# paris_relay_rev_C.net
KiCad netlist of a schematic drawn in EAGLE
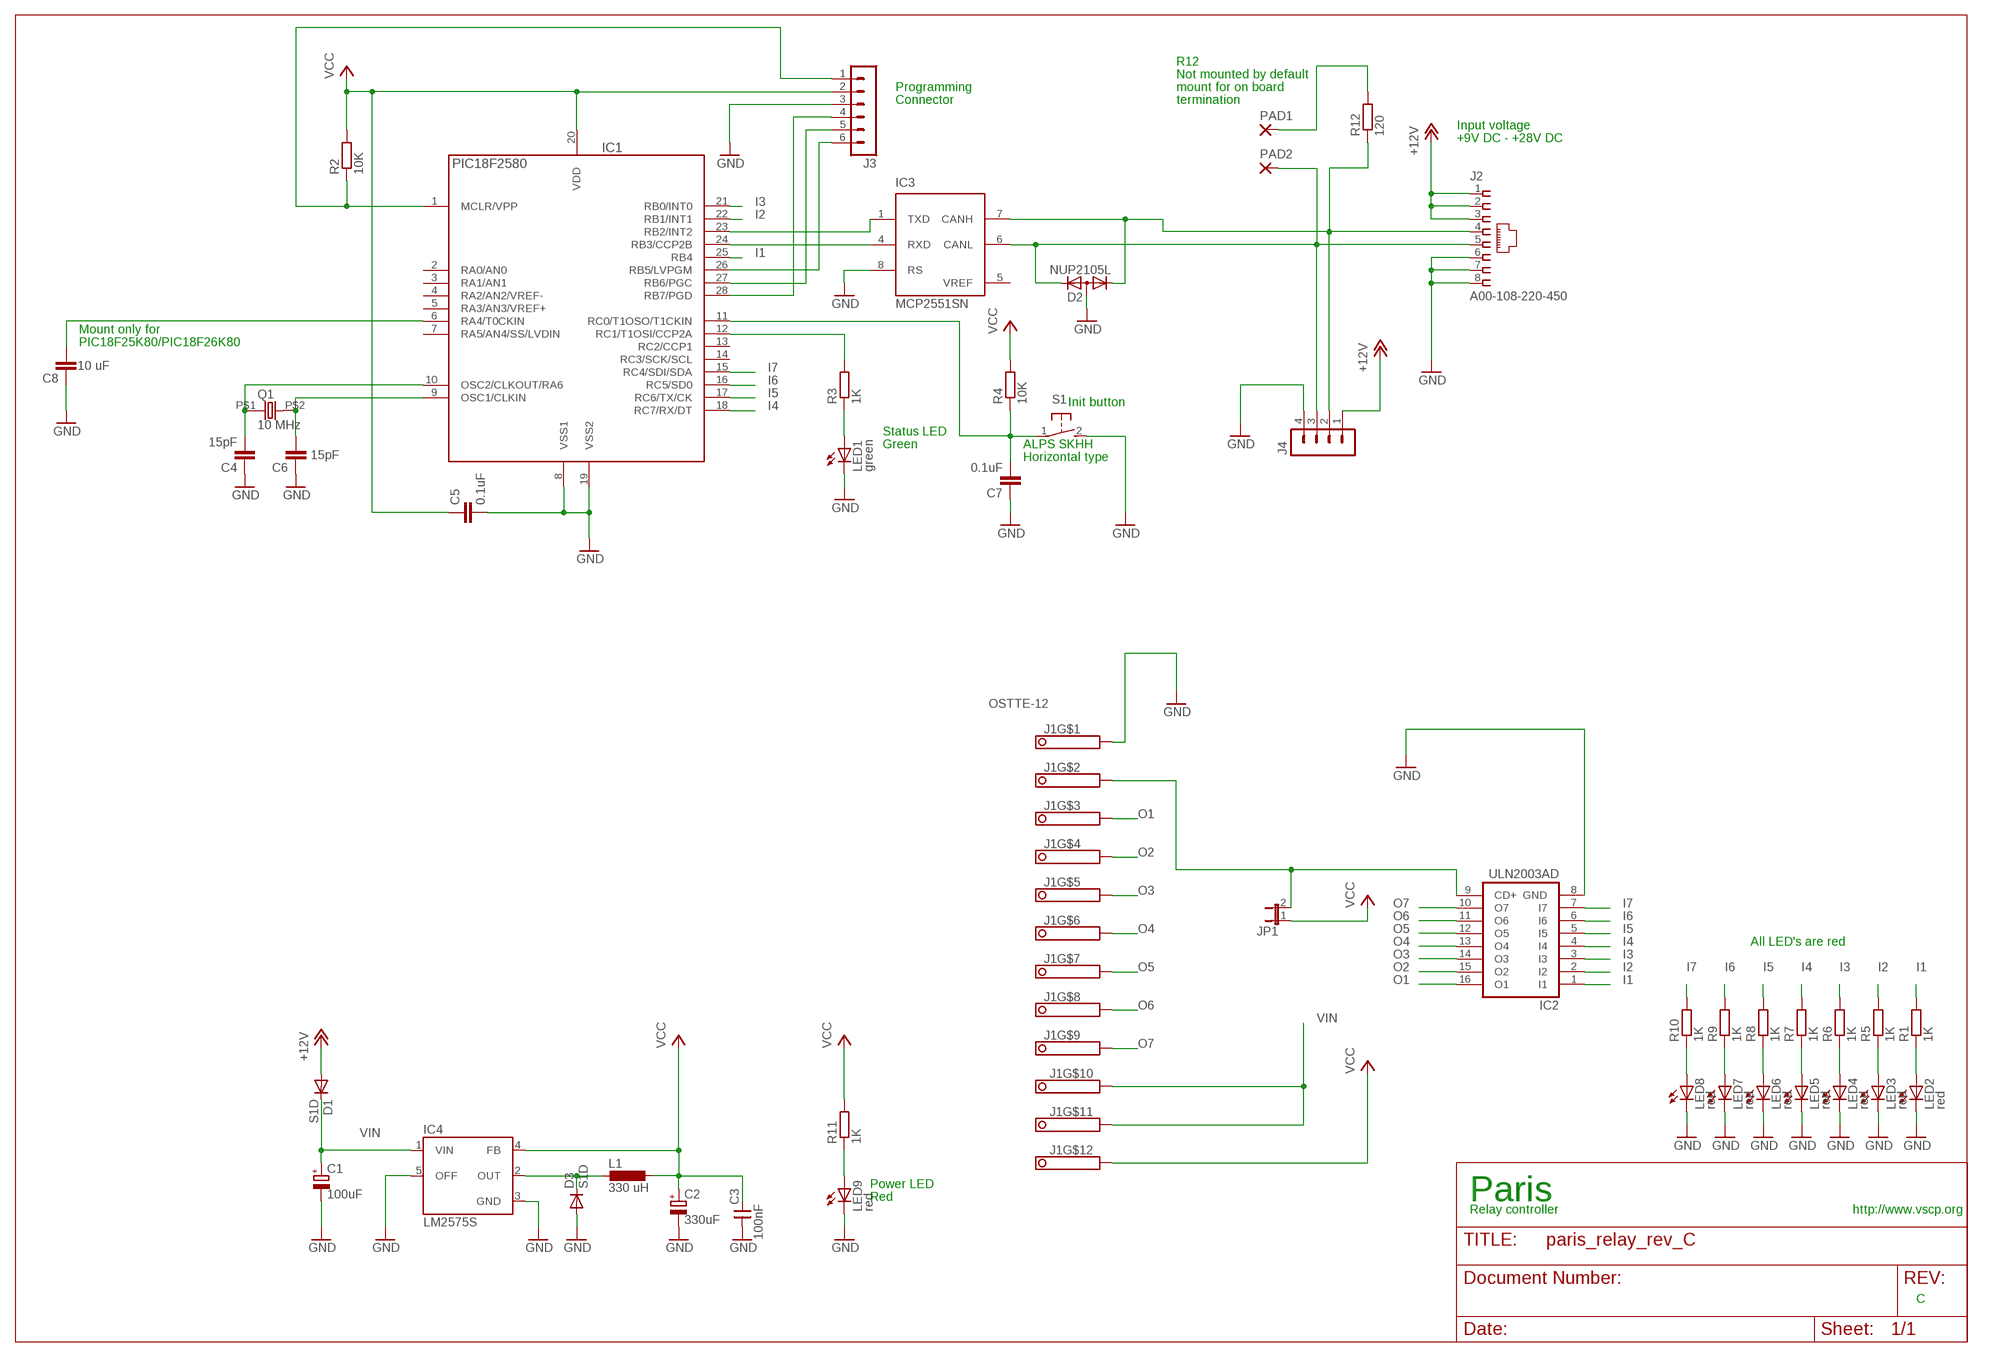
[diagram p0: schematic, sheet 1]

(export (version "E")
  (design (tool "Eeschema 10.0.6"))
  (components
    (comp (ref "C1")
      (value "100uF")
      (footprint "eagle-import:PANASONIC_D")
      (libsource (lib "eagle-import") (part "CPOL-EUD"))
    )
    (comp (ref "C2")
      (value "330uF")
      (footprint "eagle-import:PANASONIC_D")
      (libsource (lib "eagle-import") (part "CPOL-EUD"))
    )
    (comp (ref "C3")
      (value "100nF")
      (footprint "eagle-import:0805")
      (libsource (lib "eagle-import") (part "CNP-0805"))
    )
    (comp (ref "C4")
      (value "15pF")
      (footprint "eagle-import:C0805")
      (libsource (lib "eagle-import") (part "C-EUC0805"))
    )
    (comp (ref "C5")
      (value "0.1uF")
      (footprint "eagle-import:C0805")
      (libsource (lib "eagle-import") (part "C-EUC0805"))
    )
    (comp (ref "C6")
      (value "15pF")
      (footprint "eagle-import:C0805")
      (libsource (lib "eagle-import") (part "C-EUC0805"))
    )
    (comp (ref "C7")
      (value "0.1uF")
      (footprint "eagle-import:C0805")
      (libsource (lib "eagle-import") (part "C-EUC0805"))
    )
    (comp (ref "C8")
      (value "10 uF")
      (footprint "eagle-import:C0805")
      (libsource (lib "eagle-import") (part "C-EUC0805"))
    )
    (comp (ref "D1")
      (value "S1D")
      (footprint "eagle-import:SOD123")
      (libsource (lib "eagle-import") (part "DIODE-SOD123"))
    )
    (comp (ref "D2")
      (value "NUP2105L")
      (footprint "eagle-import:SOT23")
      (libsource (lib "eagle-import") (part "DIODE-2CA|ACSOT23"))
    )
    (comp (ref "D3")
      (value "S1D")
      (footprint "eagle-import:SOD123")
      (libsource (lib "eagle-import") (part "DIODE-SOD123"))
    )
    (comp (ref "IC1")
      (value "PIC18F2580")
      (footprint "eagle-import:SO28")
      (libsource (lib "eagle-import") (part "PIC18F252-?I/SOL"))
    )
    (comp (ref "IC2")
      (value "ULN2003AD")
      (footprint "eagle-import:SO16")
      (libsource (lib "eagle-import") (part "ULN2003AD"))
    )
    (comp (ref "IC3")
      (value "MCP2551SN")
      (footprint "eagle-import:SO-08")
      (libsource (lib "eagle-import") (part "MCP2551SN"))
    )
    (comp (ref "IC4")
      (value "LM2575S")
      (footprint "eagle-import:TO263-5")
      (libsource (lib "eagle-import") (part "LM2575S"))
    )
    (comp (ref "J1")
      (value "OSTTE-12")
      (footprint "eagle-import:PINHEAD-12")
      (libsource (lib "eagle-import") (part "OSTTE-12"))
    )
    (comp (ref "J2")
      (value "A00-108-220-450")
      (footprint "eagle-import:RJ-45")
      (libsource (lib "eagle-import") (part "A00-108-220-450"))
    )
    (comp (ref "J3")
      (value "MA06-1")
      (footprint "eagle-import:MA06-1")
      (libsource (lib "eagle-import") (part "MA06-1"))
    )
    (comp (ref "J4")
      (value "MA04-1")
      (footprint "eagle-import:MA04-1")
      (libsource (lib "eagle-import") (part "MA04-1"))
    )
    (comp (ref "JP1")
      (value "JP1E")
      (footprint "eagle-import:JP1")
      (libsource (lib "eagle-import") (part "JP1E"))
    )
    (comp (ref "L1")
      (value "330 uH")
      (footprint "eagle-import:DO3316P")
      (libsource (lib "eagle-import") (part "DO3316P"))
    )
    (comp (ref "LED1")
      (value "green")
      (footprint "eagle-import:CHIP-LED0805")
      (libsource (lib "eagle-import") (part "LEDCHIP-LED0805"))
    )
    (comp (ref "LED2")
      (value "red")
      (footprint "eagle-import:CHIP-LED0805")
      (libsource (lib "eagle-import") (part "LEDCHIP-LED0805"))
    )
    (comp (ref "LED3")
      (value "red")
      (footprint "eagle-import:CHIP-LED0805")
      (libsource (lib "eagle-import") (part "LEDCHIP-LED0805"))
    )
    (comp (ref "LED4")
      (value "red")
      (footprint "eagle-import:CHIP-LED0805")
      (libsource (lib "eagle-import") (part "LEDCHIP-LED0805"))
    )
    (comp (ref "LED5")
      (value "red")
      (footprint "eagle-import:CHIP-LED0805")
      (libsource (lib "eagle-import") (part "LEDCHIP-LED0805"))
    )
    (comp (ref "LED6")
      (value "red")
      (footprint "eagle-import:CHIP-LED0805")
      (libsource (lib "eagle-import") (part "LEDCHIP-LED0805"))
    )
    (comp (ref "LED7")
      (value "red")
      (footprint "eagle-import:CHIP-LED0805")
      (libsource (lib "eagle-import") (part "LEDCHIP-LED0805"))
    )
    (comp (ref "LED8")
      (value "red")
      (footprint "eagle-import:CHIP-LED0805")
      (libsource (lib "eagle-import") (part "LEDCHIP-LED0805"))
    )
    (comp (ref "LED9")
      (value "red")
      (footprint "eagle-import:CHIP-LED0805")
      (libsource (lib "eagle-import") (part "LEDCHIP-LED0805"))
    )
    (comp (ref "PAD1")
      (value "1,6/0,8")
      (footprint "eagle-import:1,6_0,8")
      (libsource (lib "eagle-import") (part "1,6/0,8"))
    )
    (comp (ref "PAD2")
      (value "1,6/0,8")
      (footprint "eagle-import:1,6_0,8")
      (libsource (lib "eagle-import") (part "1,6/0,8"))
    )
    (comp (ref "Q1")
      (value "10 MHz")
      (footprint "eagle-import:9C")
      (libsource (lib "eagle-import") (part "HC-49S"))
    )
    (comp (ref "R1")
      (value "1K")
      (footprint "eagle-import:R0805")
      (libsource (lib "eagle-import") (part "R-EU_R0805"))
    )
    (comp (ref "R2")
      (value "10K")
      (footprint "eagle-import:R0805")
      (libsource (lib "eagle-import") (part "R-EU_R0805"))
    )
    (comp (ref "R3")
      (value "1K")
      (footprint "eagle-import:R0805")
      (libsource (lib "eagle-import") (part "R-EU_R0805"))
    )
    (comp (ref "R4")
      (value "10K")
      (footprint "eagle-import:R0805")
      (libsource (lib "eagle-import") (part "R-EU_R0805"))
    )
    (comp (ref "R5")
      (value "1K")
      (footprint "eagle-import:R0805")
      (libsource (lib "eagle-import") (part "R-EU_R0805"))
    )
    (comp (ref "R6")
      (value "1K")
      (footprint "eagle-import:R0805")
      (libsource (lib "eagle-import") (part "R-EU_R0805"))
    )
    (comp (ref "R7")
      (value "1K")
      (footprint "eagle-import:R0805")
      (libsource (lib "eagle-import") (part "R-EU_R0805"))
    )
    (comp (ref "R8")
      (value "1K")
      (footprint "eagle-import:R0805")
      (libsource (lib "eagle-import") (part "R-EU_R0805"))
    )
    (comp (ref "R9")
      (value "1K")
      (footprint "eagle-import:R0805")
      (libsource (lib "eagle-import") (part "R-EU_R0805"))
    )
    (comp (ref "R10")
      (value "1K")
      (footprint "eagle-import:R0805")
      (libsource (lib "eagle-import") (part "R-EU_R0805"))
    )
    (comp (ref "R11")
      (value "1K")
      (footprint "eagle-import:R0805")
      (libsource (lib "eagle-import") (part "R-EU_R0805"))
    )
    (comp (ref "R12")
      (value "120")
      (footprint "eagle-import:R0805")
      (libsource (lib "eagle-import") (part "R-EU_R0805"))
    )
    (comp (ref "S1")
      (value "31-XX")
      (footprint "eagle-import:B3F-31XX")
      (fields (field (name "MPN") "B3F-3100"))
      (libsource (lib "eagle-import") (part "31-XX"))
    )
  )
  (nets
    (net (code "1") (name "+12V") (class "Default")
      (node (ref "D1") (pin "A") (pinfunction "A_A") (pintype "passive"))
      (node (ref "J2") (pin "1") (pinfunction "1_1") (pintype "passive"))
      (node (ref "J2") (pin "2") (pinfunction "2_2") (pintype "passive"))
      (node (ref "J2") (pin "3") (pinfunction "3_3") (pintype "passive"))
      (node (ref "J4") (pin "1") (pinfunction "1_1") (pintype "passive"))
    )
    (net (code "2") (name "/I1") (class "Default")
      (node (ref "IC1") (pin "25") (pinfunction "RB4_25") (pintype "bidirectional"))
      (node (ref "IC2") (pin "1") (pinfunction "I1_1") (pintype "input"))
      (node (ref "R1") (pin "2") (pinfunction "2_2") (pintype "passive"))
    )
    (net (code "3") (name "/I2") (class "Default")
      (node (ref "IC1") (pin "22") (pinfunction "RB1/INT1_22") (pintype "bidirectional"))
      (node (ref "IC2") (pin "2") (pinfunction "I2_2") (pintype "input"))
      (node (ref "R5") (pin "2") (pinfunction "2_2") (pintype "passive"))
    )
    (net (code "4") (name "/I3") (class "Default")
      (node (ref "IC1") (pin "21") (pinfunction "RB0/INT0_21") (pintype "bidirectional"))
      (node (ref "IC2") (pin "3") (pinfunction "I3_3") (pintype "input"))
      (node (ref "R6") (pin "2") (pinfunction "2_2") (pintype "passive"))
    )
    (net (code "5") (name "/I4") (class "Default")
      (node (ref "IC1") (pin "18") (pinfunction "RC7/RX/DT_18") (pintype "bidirectional"))
      (node (ref "IC2") (pin "4") (pinfunction "I4_4") (pintype "input"))
      (node (ref "R7") (pin "2") (pinfunction "2_2") (pintype "passive"))
    )
    (net (code "6") (name "/I5") (class "Default")
      (node (ref "IC1") (pin "17") (pinfunction "RC6/TX/CK_17") (pintype "bidirectional"))
      (node (ref "IC2") (pin "5") (pinfunction "I5_5") (pintype "input"))
      (node (ref "R8") (pin "2") (pinfunction "2_2") (pintype "passive"))
    )
    (net (code "7") (name "/I6") (class "Default")
      (node (ref "IC1") (pin "16") (pinfunction "RC5/SD0_16") (pintype "bidirectional"))
      (node (ref "IC2") (pin "6") (pinfunction "I6_6") (pintype "input"))
      (node (ref "R9") (pin "2") (pinfunction "2_2") (pintype "passive"))
    )
    (net (code "8") (name "/I7") (class "Default")
      (node (ref "IC1") (pin "15") (pinfunction "RC4/SDI/SDA_15") (pintype "bidirectional"))
      (node (ref "IC2") (pin "7") (pinfunction "I7_7") (pintype "input"))
      (node (ref "R10") (pin "2") (pinfunction "2_2") (pintype "passive"))
    )
    (net (code "9") (name "/O1") (class "Default")
      (node (ref "IC2") (pin "16") (pinfunction "O1_16") (pintype "open_collector"))
      (node (ref "J1") (pin "3") (pinfunction "K_3") (pintype "passive"))
    )
    (net (code "10") (name "/O2") (class "Default")
      (node (ref "IC2") (pin "15") (pinfunction "O2_15") (pintype "open_collector"))
      (node (ref "J1") (pin "4") (pinfunction "K_4") (pintype "passive"))
    )
    (net (code "11") (name "/O3") (class "Default")
      (node (ref "IC2") (pin "14") (pinfunction "O3_14") (pintype "open_collector"))
      (node (ref "J1") (pin "5") (pinfunction "K_5") (pintype "passive"))
    )
    (net (code "12") (name "/O4") (class "Default")
      (node (ref "IC2") (pin "13") (pinfunction "O4_13") (pintype "open_collector"))
      (node (ref "J1") (pin "6") (pinfunction "K_6") (pintype "passive"))
    )
    (net (code "13") (name "/O5") (class "Default")
      (node (ref "IC2") (pin "12") (pinfunction "O5_12") (pintype "open_collector"))
      (node (ref "J1") (pin "7") (pinfunction "K_7") (pintype "passive"))
    )
    (net (code "14") (name "/O6") (class "Default")
      (node (ref "IC2") (pin "11") (pinfunction "O6_11") (pintype "open_collector"))
      (node (ref "J1") (pin "8") (pinfunction "K_8") (pintype "passive"))
    )
    (net (code "15") (name "/O7") (class "Default")
      (node (ref "IC2") (pin "10") (pinfunction "O7_10") (pintype "open_collector"))
      (node (ref "J1") (pin "9") (pinfunction "K_9") (pintype "passive"))
    )
    (net (code "16") (name "/VIN") (class "Default")
      (node (ref "C1") (pin "+") (pinfunction "+_+") (pintype "passive"))
      (node (ref "D1") (pin "C") (pinfunction "C_C") (pintype "passive"))
      (node (ref "IC4") (pin "1") (pinfunction "VIN_1") (pintype "power_in"))
      (node (ref "J1") (pin "10") (pinfunction "K_10") (pintype "passive"))
      (node (ref "J1") (pin "11") (pinfunction "K_11") (pintype "passive"))
    )
    (net (code "17") (name "/VREF") (class "Default")
      (node (ref "IC3") (pin "5") (pinfunction "VREF_5") (pintype "power_in"))
    )
    (net (code "18") (name "GND") (class "Default")
      (node (ref "C1") (pin "-") (pinfunction "-_-") (pintype "passive"))
      (node (ref "C2") (pin "-") (pinfunction "-_-") (pintype "passive"))
      (node (ref "C3") (pin "1") (pinfunction "1_1") (pintype "passive"))
      (node (ref "C4") (pin "1") (pinfunction "1_1") (pintype "passive"))
      (node (ref "C5") (pin "2") (pinfunction "2_2") (pintype "passive"))
      (node (ref "C6") (pin "1") (pinfunction "1_1") (pintype "passive"))
      (node (ref "C7") (pin "1") (pinfunction "1_1") (pintype "passive"))
      (node (ref "C8") (pin "1") (pinfunction "1_1") (pintype "passive"))
      (node (ref "D2") (pin "3") (pinfunction "A_3") (pintype "passive"))
      (node (ref "D3") (pin "A") (pinfunction "A_A") (pintype "passive"))
      (node (ref "IC1") (pin "19") (pinfunction "VSS2_19") (pintype "power_in"))
      (node (ref "IC1") (pin "8") (pinfunction "VSS1_8") (pintype "power_in"))
      (node (ref "IC2") (pin "8") (pinfunction "GND_8") (pintype "power_in"))
      (node (ref "IC3") (pin "8") (pinfunction "RS_8") (pintype "input"))
      (node (ref "IC4") (pin "3") (pinfunction "GND_3") (pintype "power_in"))
      (node (ref "IC4") (pin "5") (pinfunction "OFF_5") (pintype "input"))
      (node (ref "J1") (pin "1") (pinfunction "K_1") (pintype "passive"))
      (node (ref "J2") (pin "6") (pinfunction "6_6") (pintype "passive"))
      (node (ref "J2") (pin "7") (pinfunction "7_7") (pintype "passive"))
      (node (ref "J2") (pin "8") (pinfunction "8_8") (pintype "passive"))
      (node (ref "J3") (pin "3") (pinfunction "3_3") (pintype "passive"))
      (node (ref "J4") (pin "4") (pinfunction "4_4") (pintype "passive"))
      (node (ref "LED1") (pin "C") (pinfunction "C_C") (pintype "passive"))
      (node (ref "LED2") (pin "C") (pinfunction "C_C") (pintype "passive"))
      (node (ref "LED3") (pin "C") (pinfunction "C_C") (pintype "passive"))
      (node (ref "LED4") (pin "C") (pinfunction "C_C") (pintype "passive"))
      (node (ref "LED5") (pin "C") (pinfunction "C_C") (pintype "passive"))
      (node (ref "LED6") (pin "C") (pinfunction "C_C") (pintype "passive"))
      (node (ref "LED7") (pin "C") (pinfunction "C_C") (pintype "passive"))
      (node (ref "LED8") (pin "C") (pinfunction "C_C") (pintype "passive"))
      (node (ref "LED9") (pin "C") (pinfunction "C_C") (pintype "passive"))
      (node (ref "S1") (pin "2") (pinfunction "S_2") (pintype "passive"))
    )
    (net (code "19") (name "Net-(D2-K1)") (class "Default")
      (node (ref "D2") (pin "1") (pinfunction "K1_1") (pintype "passive"))
      (node (ref "IC3") (pin "7") (pinfunction "CANH_7") (pintype "bidirectional"))
      (node (ref "J2") (pin "4") (pinfunction "4_4") (pintype "passive"))
      (node (ref "J4") (pin "2") (pinfunction "2_2") (pintype "passive"))
      (node (ref "R12") (pin "1") (pinfunction "1_1") (pintype "passive"))
    )
    (net (code "20") (name "Net-(D2-K2)") (class "Default")
      (node (ref "D2") (pin "2") (pinfunction "K2_2") (pintype "passive"))
      (node (ref "IC3") (pin "6") (pinfunction "CANL_6") (pintype "bidirectional"))
      (node (ref "J2") (pin "5") (pinfunction "5_5") (pintype "passive"))
      (node (ref "J4") (pin "3") (pinfunction "3_3") (pintype "passive"))
      (node (ref "PAD2") (pin "1") (pinfunction "P_1") (pintype "passive"))
    )
    (net (code "21") (name "Net-(IC1-MCLR{slash}VPP)") (class "Default")
      (node (ref "IC1") (pin "1") (pinfunction "MCLR/VPP_1") (pintype "input"))
      (node (ref "J3") (pin "1") (pinfunction "1_1") (pintype "passive"))
      (node (ref "R2") (pin "1") (pinfunction "1_1") (pintype "passive"))
    )
    (net (code "22") (name "Net-(IC1-OSC1{slash}CLKIN)") (class "Default")
      (node (ref "C6") (pin "2") (pinfunction "2_2") (pintype "passive"))
      (node (ref "IC1") (pin "9") (pinfunction "OSC1/CLKIN_9") (pintype "input"))
      (node (ref "Q1") (pin "P$2") (pinfunction "2_P$2") (pintype "passive"))
    )
    (net (code "23") (name "Net-(IC1-OSC2{slash}CLKOUT{slash}RA6)") (class "Default")
      (node (ref "C4") (pin "2") (pinfunction "2_2") (pintype "passive"))
      (node (ref "IC1") (pin "10") (pinfunction "OSC2/CLKOUT/RA6_10") (pintype "output"))
      (node (ref "Q1") (pin "P$1") (pinfunction "1_P$1") (pintype "passive"))
    )
    (net (code "24") (name "Net-(IC1-RA4{slash}T0CKIN)") (class "Default")
      (node (ref "C8") (pin "2") (pinfunction "2_2") (pintype "passive"))
      (node (ref "IC1") (pin "6") (pinfunction "RA4/T0CKIN_6") (pintype "open_collector"))
    )
    (net (code "25") (name "Net-(IC1-RB2{slash}INT2)") (class "Default")
      (node (ref "IC1") (pin "23") (pinfunction "RB2/INT2_23") (pintype "bidirectional"))
      (node (ref "IC3") (pin "1") (pinfunction "TXD_1") (pintype "input"))
    )
    (net (code "26") (name "Net-(IC1-RB3{slash}CCP2B)") (class "Default")
      (node (ref "IC1") (pin "24") (pinfunction "RB3/CCP2B_24") (pintype "bidirectional"))
      (node (ref "IC3") (pin "4") (pinfunction "RXD_4") (pintype "output"))
    )
    (net (code "27") (name "Net-(IC1-RB5{slash}LVPGM)") (class "Default")
      (node (ref "IC1") (pin "26") (pinfunction "RB5/LVPGM_26") (pintype "bidirectional"))
      (node (ref "J3") (pin "6") (pinfunction "6_6") (pintype "passive"))
    )
    (net (code "28") (name "Net-(IC1-RB6{slash}PGC)") (class "Default")
      (node (ref "IC1") (pin "27") (pinfunction "RB6/PGC_27") (pintype "bidirectional"))
      (node (ref "J3") (pin "5") (pinfunction "5_5") (pintype "passive"))
    )
    (net (code "29") (name "Net-(IC1-RB7{slash}PGD)") (class "Default")
      (node (ref "IC1") (pin "28") (pinfunction "RB7/PGD_28") (pintype "bidirectional"))
      (node (ref "J3") (pin "4") (pinfunction "4_4") (pintype "passive"))
    )
    (net (code "30") (name "Net-(IC1-RC0{slash}T1OSO{slash}T1CKIN)") (class "Default")
      (node (ref "C7") (pin "2") (pinfunction "2_2") (pintype "passive"))
      (node (ref "IC1") (pin "11") (pinfunction "RC0/T1OSO/T1CKIN_11") (pintype "bidirectional"))
      (node (ref "R4") (pin "1") (pinfunction "1_1") (pintype "passive"))
      (node (ref "S1") (pin "1") (pinfunction "P_1") (pintype "passive"))
    )
    (net (code "31") (name "Net-(IC1-RC1{slash}T1OSI{slash}CCP2A)") (class "Default")
      (node (ref "IC1") (pin "12") (pinfunction "RC1/T1OSI/CCP2A_12") (pintype "bidirectional"))
      (node (ref "R3") (pin "2") (pinfunction "2_2") (pintype "passive"))
    )
    (net (code "32") (name "Net-(IC2-CD+)") (class "Default")
      (node (ref "IC2") (pin "9") (pinfunction "CD+_9") (pintype "passive"))
      (node (ref "J1") (pin "2") (pinfunction "K_2") (pintype "passive"))
      (node (ref "JP1") (pin "2") (pinfunction "2_2") (pintype "passive"))
    )
    (net (code "33") (name "Net-(IC4-OUT)") (class "Default")
      (node (ref "D3") (pin "C") (pinfunction "C_C") (pintype "passive"))
      (node (ref "IC4") (pin "2") (pinfunction "OUT_2") (pintype "output"))
      (node (ref "L1") (pin "1") (pinfunction "1_1") (pintype "passive"))
    )
    (net (code "34") (name "Net-(LED1-PadA)") (class "Default")
      (node (ref "LED1") (pin "A") (pinfunction "A_A") (pintype "passive"))
      (node (ref "R3") (pin "1") (pinfunction "1_1") (pintype "passive"))
    )
    (net (code "35") (name "Net-(LED2-PadA)") (class "Default")
      (node (ref "LED2") (pin "A") (pinfunction "A_A") (pintype "passive"))
      (node (ref "R1") (pin "1") (pinfunction "1_1") (pintype "passive"))
    )
    (net (code "36") (name "Net-(LED3-PadA)") (class "Default")
      (node (ref "LED3") (pin "A") (pinfunction "A_A") (pintype "passive"))
      (node (ref "R5") (pin "1") (pinfunction "1_1") (pintype "passive"))
    )
    (net (code "37") (name "Net-(LED4-PadA)") (class "Default")
      (node (ref "LED4") (pin "A") (pinfunction "A_A") (pintype "passive"))
      (node (ref "R6") (pin "1") (pinfunction "1_1") (pintype "passive"))
    )
    (net (code "38") (name "Net-(LED5-PadA)") (class "Default")
      (node (ref "LED5") (pin "A") (pinfunction "A_A") (pintype "passive"))
      (node (ref "R7") (pin "1") (pinfunction "1_1") (pintype "passive"))
    )
    (net (code "39") (name "Net-(LED6-PadA)") (class "Default")
      (node (ref "LED6") (pin "A") (pinfunction "A_A") (pintype "passive"))
      (node (ref "R8") (pin "1") (pinfunction "1_1") (pintype "passive"))
    )
    (net (code "40") (name "Net-(LED7-PadA)") (class "Default")
      (node (ref "LED7") (pin "A") (pinfunction "A_A") (pintype "passive"))
      (node (ref "R9") (pin "1") (pinfunction "1_1") (pintype "passive"))
    )
    (net (code "41") (name "Net-(LED8-PadA)") (class "Default")
      (node (ref "LED8") (pin "A") (pinfunction "A_A") (pintype "passive"))
      (node (ref "R10") (pin "1") (pinfunction "1_1") (pintype "passive"))
    )
    (net (code "42") (name "Net-(LED9-PadA)") (class "Default")
      (node (ref "LED9") (pin "A") (pinfunction "A_A") (pintype "passive"))
      (node (ref "R11") (pin "1") (pinfunction "1_1") (pintype "passive"))
    )
    (net (code "43") (name "Net-(PAD1-P)") (class "Default")
      (node (ref "PAD1") (pin "1") (pinfunction "P_1") (pintype "passive"))
      (node (ref "R12") (pin "2") (pinfunction "2_2") (pintype "passive"))
    )
    (net (code "44") (name "VCC") (class "Default")
      (node (ref "C2") (pin "+") (pinfunction "+_+") (pintype "passive"))
      (node (ref "C3") (pin "2") (pinfunction "2_2") (pintype "passive"))
      (node (ref "C5") (pin "1") (pinfunction "1_1") (pintype "passive"))
      (node (ref "IC1") (pin "20") (pinfunction "VDD_20") (pintype "power_in"))
      (node (ref "IC4") (pin "4") (pinfunction "FB_4") (pintype "input"))
      (node (ref "J1") (pin "12") (pinfunction "K_12") (pintype "passive"))
      (node (ref "J3") (pin "2") (pinfunction "2_2") (pintype "passive"))
      (node (ref "JP1") (pin "1") (pinfunction "1_1") (pintype "passive"))
      (node (ref "L1") (pin "2") (pinfunction "2_2") (pintype "passive"))
      (node (ref "R11") (pin "2") (pinfunction "2_2") (pintype "passive"))
      (node (ref "R2") (pin "2") (pinfunction "2_2") (pintype "passive"))
      (node (ref "R4") (pin "2") (pinfunction "2_2") (pintype "passive"))
    )
    (net (code "45") (name "unconnected-(IC1-RA0{slash}AN0-Pad2)") (class "Default")
      (node (ref "IC1") (pin "2") (pinfunction "RA0/AN0_2") (pintype "bidirectional"))
    )
    (net (code "46") (name "unconnected-(IC1-RA1{slash}AN1-Pad3)") (class "Default")
      (node (ref "IC1") (pin "3") (pinfunction "RA1/AN1_3") (pintype "bidirectional"))
    )
    (net (code "47") (name "unconnected-(IC1-RA2{slash}AN2{slash}VREF--Pad4)") (class "Default")
      (node (ref "IC1") (pin "4") (pinfunction "RA2/AN2/VREF-_4") (pintype "bidirectional"))
    )
    (net (code "48") (name "unconnected-(IC1-RA3{slash}AN3{slash}VREF+-Pad5)") (class "Default")
      (node (ref "IC1") (pin "5") (pinfunction "RA3/AN3/VREF+_5") (pintype "bidirectional"))
    )
    (net (code "49") (name "unconnected-(IC1-RA5{slash}AN4{slash}SS{slash}LVDIN-Pad7)") (class "Default")
      (node (ref "IC1") (pin "7") (pinfunction "RA5/AN4/SS/LVDIN_7") (pintype "bidirectional"))
    )
    (net (code "50") (name "unconnected-(IC1-RC2{slash}CCP1-Pad13)") (class "Default")
      (node (ref "IC1") (pin "13") (pinfunction "RC2/CCP1_13") (pintype "bidirectional"))
    )
    (net (code "51") (name "unconnected-(IC1-RC3{slash}SCK{slash}SCL-Pad14)") (class "Default")
      (node (ref "IC1") (pin "14") (pinfunction "RC3/SCK/SCL_14") (pintype "bidirectional"))
    )
  )
)
